# Thermometer.net
KiCad netlist of a schematic drawn in Altium Designer
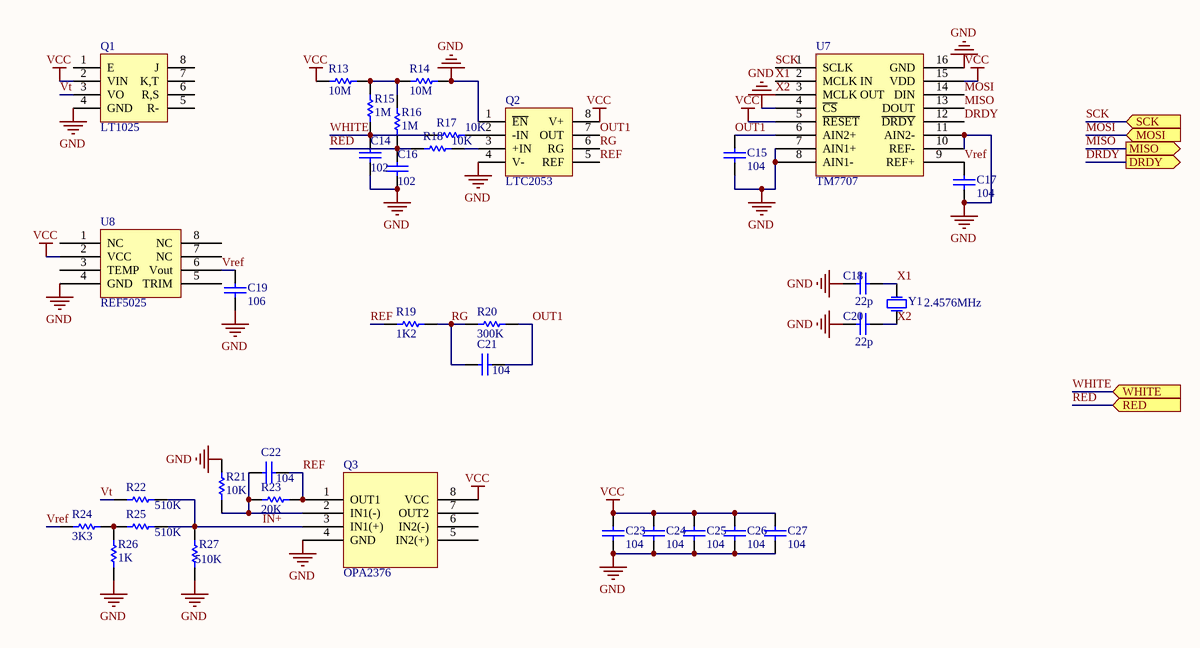
[diagram p0: Thermometer.SchDoc]

(export (version "E")
  (design (tool "Eeschema 10.0.6"))
  (components
    (comp (ref "C14")
      (value "102")
      (footprint "CR2012-0805")
      (description "Capacitor")
      (fields (field (name "Comment") "Cap") (field (name "PUBLISHER") "Altium Limited"))
      (libsource (lib "ComDev") (part "Cap"))
    )
    (comp (ref "C15")
      (value "104")
      (footprint "CR2012-0805")
      (description "Capacitor")
      (fields (field (name "Comment") "Cap") (field (name "PUBLISHER") "Altium Limited"))
      (libsource (lib "ComDev") (part "Cap"))
    )
    (comp (ref "C16")
      (value "102")
      (footprint "CR2012-0805")
      (description "Capacitor")
      (fields (field (name "Comment") "Cap") (field (name "PUBLISHER") "Altium Limited"))
      (libsource (lib "ComDev") (part "Cap"))
    )
    (comp (ref "C17")
      (value "104")
      (footprint "CR2012-0805")
      (description "Capacitor")
      (fields (field (name "Comment") "Cap") (field (name "PUBLISHER") "Altium Limited"))
      (libsource (lib "ComDev") (part "Cap"))
    )
    (comp (ref "C18")
      (value "22p")
      (footprint "CR2012-0805")
      (description "Capacitor")
      (fields (field (name "Comment") "Cap") (field (name "PUBLISHER") "Altium Limited"))
      (libsource (lib "ComDev") (part "Cap"))
    )
    (comp (ref "C19")
      (value "106")
      (footprint "CC3216-1206")
      (description "Capacitor")
      (fields (field (name "Comment") "Cap") (field (name "PUBLISHER") "Altium Limited"))
      (libsource (lib "ComDev") (part "Cap"))
    )
    (comp (ref "C20")
      (value "22p")
      (footprint "CR2012-0805")
      (description "Capacitor")
      (fields (field (name "Comment") "Cap") (field (name "PUBLISHER") "Altium Limited"))
      (libsource (lib "ComDev") (part "Cap"))
    )
    (comp (ref "C21")
      (value "104")
      (footprint "CR2012-0805")
      (description "Capacitor")
      (fields (field (name "Comment") "Cap") (field (name "PUBLISHER") "Altium Limited"))
      (libsource (lib "ComDev") (part "Cap"))
    )
    (comp (ref "C22")
      (value "104")
      (footprint "CR2012-0805")
      (description "Capacitor")
      (fields (field (name "Comment") "Cap") (field (name "PUBLISHER") "Altium Limited"))
      (libsource (lib "ComDev") (part "Cap"))
    )
    (comp (ref "C23")
      (value "104")
      (footprint "CR2012-0805")
      (description "Capacitor")
      (fields (field (name "Comment") "Cap") (field (name "PUBLISHER") "Altium Limited"))
      (libsource (lib "ComDev") (part "Cap"))
    )
    (comp (ref "C24")
      (value "104")
      (footprint "CR2012-0805")
      (description "Capacitor")
      (fields (field (name "Comment") "Cap") (field (name "PUBLISHER") "Altium Limited"))
      (libsource (lib "ComDev") (part "Cap"))
    )
    (comp (ref "C25")
      (value "104")
      (footprint "CR2012-0805")
      (description "Capacitor")
      (fields (field (name "Comment") "Cap") (field (name "PUBLISHER") "Altium Limited"))
      (libsource (lib "ComDev") (part "Cap"))
    )
    (comp (ref "C26")
      (value "104")
      (footprint "CR2012-0805")
      (description "Capacitor")
      (fields (field (name "Comment") "Cap") (field (name "PUBLISHER") "Altium Limited"))
      (libsource (lib "ComDev") (part "Cap"))
    )
    (comp (ref "C27")
      (value "104")
      (footprint "CR2012-0805")
      (description "Capacitor")
      (fields (field (name "Comment") "Cap") (field (name "PUBLISHER") "Altium Limited"))
      (libsource (lib "ComDev") (part "Cap"))
    )
    (comp (ref "Q1") (value "LT1025") (footprint "SO-G8") (libsource (lib "Sensor") (part "LT1025")))
    (comp (ref "Q2") (value "LTC2053") (footprint "MSOP-8") (libsource (lib "AMP") (part "LTC2053")))
    (comp (ref "Q3") (value "OPA2376") (footprint "SO-G8") (libsource (lib "AMP") (part "Double_AMP")))
    (comp (ref "R13")
      (value "10M")
      (footprint "CR2012-0805")
      (description "Resistor")
      (fields (field (name "Comment") "Res") (field (name "PUBLISHER") "Altium Limited"))
      (libsource (lib "ComDev") (part "Res"))
    )
    (comp (ref "R14")
      (value "10M")
      (footprint "CR2012-0805")
      (description "Resistor")
      (fields (field (name "Comment") "Res") (field (name "PUBLISHER") "Altium Limited"))
      (libsource (lib "ComDev") (part "Res"))
    )
    (comp (ref "R15")
      (value "1M")
      (footprint "CR2012-0805")
      (description "Resistor")
      (fields (field (name "Comment") "Res") (field (name "PUBLISHER") "Altium Limited"))
      (libsource (lib "ComDev") (part "Res"))
    )
    (comp (ref "R16")
      (value "1M")
      (footprint "CR2012-0805")
      (description "Resistor")
      (fields (field (name "Comment") "Res") (field (name "PUBLISHER") "Altium Limited"))
      (libsource (lib "ComDev") (part "Res"))
    )
    (comp (ref "R17")
      (value "10K")
      (footprint "CR2012-0805")
      (description "Resistor")
      (fields (field (name "Comment") "Res") (field (name "PUBLISHER") "Altium Limited"))
      (libsource (lib "ComDev") (part "Res"))
    )
    (comp (ref "R18")
      (value "10K")
      (footprint "CR2012-0805")
      (description "Resistor")
      (fields (field (name "Comment") "Res") (field (name "PUBLISHER") "Altium Limited"))
      (libsource (lib "ComDev") (part "Res"))
    )
    (comp (ref "R19")
      (value "1K2")
      (footprint "CR2012-0805")
      (description "Resistor")
      (fields (field (name "Comment") "Res") (field (name "PUBLISHER") "Altium Limited"))
      (libsource (lib "ComDev") (part "Res"))
    )
    (comp (ref "R20")
      (value "300K")
      (footprint "CR2012-0805")
      (description "Resistor")
      (fields (field (name "Comment") "Res") (field (name "PUBLISHER") "Altium Limited"))
      (libsource (lib "ComDev") (part "Res"))
    )
    (comp (ref "R21")
      (value "10K")
      (footprint "CR2012-0805")
      (description "Resistor")
      (fields (field (name "Comment") "Res") (field (name "PUBLISHER") "Altium Limited"))
      (libsource (lib "ComDev") (part "Res"))
    )
    (comp (ref "R22")
      (value "510K")
      (footprint "CR2012-0805")
      (description "Resistor")
      (fields (field (name "Comment") "Res") (field (name "PUBLISHER") "Altium Limited"))
      (libsource (lib "ComDev") (part "Res"))
    )
    (comp (ref "R23")
      (value "20K")
      (footprint "CR2012-0805")
      (description "Resistor")
      (fields (field (name "Comment") "Res") (field (name "PUBLISHER") "Altium Limited"))
      (libsource (lib "ComDev") (part "Res"))
    )
    (comp (ref "R24")
      (value "3K3")
      (footprint "CR2012-0805")
      (description "Resistor")
      (fields (field (name "Comment") "Res") (field (name "PUBLISHER") "Altium Limited"))
      (libsource (lib "ComDev") (part "Res"))
    )
    (comp (ref "R25")
      (value "510K")
      (footprint "CR2012-0805")
      (description "Resistor")
      (fields (field (name "Comment") "Res") (field (name "PUBLISHER") "Altium Limited"))
      (libsource (lib "ComDev") (part "Res"))
    )
    (comp (ref "R26")
      (value "1K")
      (footprint "CR2012-0805")
      (description "Resistor")
      (fields (field (name "Comment") "Res") (field (name "PUBLISHER") "Altium Limited"))
      (libsource (lib "ComDev") (part "Res"))
    )
    (comp (ref "R27")
      (value "510K")
      (footprint "CR2012-0805")
      (description "Resistor")
      (fields (field (name "Comment") "Res") (field (name "PUBLISHER") "Altium Limited"))
      (libsource (lib "ComDev") (part "Res"))
    )
    (comp (ref "U7") (value "TM7707") (footprint "SO-G16/D10") (libsource (lib "adc") (part "TM7707")))
    (comp (ref "U8") (value "REF5025") (footprint "SO-G8") (libsource (lib "Power") (part "REF5025")))
    (comp (ref "Y1")
      (value "XTAL")
      (footprint "XTAL")
      (description "Crystal Oscillator")
      (fields (field (name "FREQUANCY") "2.4576MHz") (field (name "PUBLISHER") "Altium Limited"))
      (libsource (lib "ComDev") (part "XTAL"))
    )
  )
  (nets
    (net (code "1") (name "/DRDY") (class "Default")
      (node (ref "U7") (pin "12") (pinfunction "~{DRDY}_12") (pintype "passive"))
    )
    (net (code "2") (name "/IN+") (class "Default")
      (node (ref "Q3") (pin "3") (pinfunction "IN1(+)_3") (pintype "passive"))
      (node (ref "R22") (pin "2") (pinfunction "2_2") (pintype "passive"))
      (node (ref "R25") (pin "2") (pinfunction "2_2") (pintype "passive"))
      (node (ref "R27") (pin "2") (pinfunction "2_2") (pintype "passive"))
    )
    (net (code "3") (name "/MISO") (class "Default")
      (node (ref "U7") (pin "13") (pinfunction "DOUT_13") (pintype "passive"))
    )
    (net (code "4") (name "/MOSI") (class "Default")
      (node (ref "U7") (pin "14") (pinfunction "DIN_14") (pintype "passive"))
    )
    (net (code "5") (name "/OUT1") (class "Default")
      (node (ref "C15") (pin "1") (pinfunction "1_1") (pintype "passive"))
      (node (ref "C21") (pin "1") (pinfunction "1_1") (pintype "passive"))
      (node (ref "Q2") (pin "7") (pinfunction "OUT_7") (pintype "passive"))
      (node (ref "R20") (pin "2") (pinfunction "2_2") (pintype "passive"))
      (node (ref "U7") (pin "6") (pinfunction "AIN2+_6") (pintype "passive"))
    )
    (net (code "6") (name "/RED") (class "Default")
      (node (ref "C16") (pin "2") (pinfunction "2_2") (pintype "passive"))
      (node (ref "R16") (pin "1") (pinfunction "1_1") (pintype "passive"))
      (node (ref "R18") (pin "1") (pinfunction "1_1") (pintype "passive"))
    )
    (net (code "7") (name "/REF") (class "Default")
      (node (ref "C22") (pin "1") (pinfunction "1_1") (pintype "passive"))
      (node (ref "Q2") (pin "5") (pinfunction "REF_5") (pintype "passive"))
      (node (ref "Q3") (pin "1") (pinfunction "OUT1_1") (pintype "passive"))
      (node (ref "R19") (pin "1") (pinfunction "1_1") (pintype "passive"))
      (node (ref "R23") (pin "1") (pinfunction "1_1") (pintype "passive"))
    )
    (net (code "8") (name "/RG") (class "Default")
      (node (ref "C21") (pin "2") (pinfunction "2_2") (pintype "passive"))
      (node (ref "Q2") (pin "6") (pinfunction "RG_6") (pintype "passive"))
      (node (ref "R19") (pin "2") (pinfunction "2_2") (pintype "passive"))
      (node (ref "R20") (pin "1") (pinfunction "1_1") (pintype "passive"))
    )
    (net (code "9") (name "/SCK") (class "Default")
      (node (ref "U7") (pin "1") (pinfunction "SCLK_1") (pintype "passive"))
    )
    (net (code "10") (name "/Vref") (class "Default")
      (node (ref "C17") (pin "2") (pinfunction "2_2") (pintype "passive"))
      (node (ref "C19") (pin "2") (pinfunction "2_2") (pintype "passive"))
      (node (ref "R24") (pin "1") (pinfunction "1_1") (pintype "passive"))
      (node (ref "U7") (pin "9") (pinfunction "REF+_9") (pintype "passive"))
      (node (ref "U8") (pin "6") (pinfunction "Vout_6") (pintype "passive"))
    )
    (net (code "11") (name "/Vt") (class "Default")
      (node (ref "Q1") (pin "3") (pinfunction "VO_3") (pintype "passive"))
      (node (ref "R22") (pin "1") (pinfunction "1_1") (pintype "passive"))
    )
    (net (code "12") (name "/WHITE") (class "Default")
      (node (ref "C14") (pin "2") (pinfunction "2_2") (pintype "passive"))
      (node (ref "R15") (pin "1") (pinfunction "1_1") (pintype "passive"))
      (node (ref "R17") (pin "1") (pinfunction "1_1") (pintype "passive"))
    )
    (net (code "13") (name "/X1") (class "Default")
      (node (ref "C18") (pin "2") (pinfunction "2_2") (pintype "passive"))
      (node (ref "U7") (pin "2") (pinfunction "MCLK_IN_2") (pintype "passive"))
      (node (ref "Y1") (pin "2") (pinfunction "OSC2_2") (pintype "passive"))
    )
    (net (code "14") (name "/X2") (class "Default")
      (node (ref "C20") (pin "2") (pinfunction "2_2") (pintype "passive"))
      (node (ref "U7") (pin "3") (pinfunction "MCLK_OUT_3") (pintype "passive"))
      (node (ref "Y1") (pin "1") (pinfunction "OSC1_1") (pintype "passive"))
    )
    (net (code "15") (name "GND") (class "Default")
      (node (ref "C14") (pin "1") (pinfunction "1_1") (pintype "passive"))
      (node (ref "C15") (pin "2") (pinfunction "2_2") (pintype "passive"))
      (node (ref "C16") (pin "1") (pinfunction "1_1") (pintype "passive"))
      (node (ref "C17") (pin "1") (pinfunction "1_1") (pintype "passive"))
      (node (ref "C18") (pin "1") (pinfunction "1_1") (pintype "passive"))
      (node (ref "C19") (pin "1") (pinfunction "1_1") (pintype "passive"))
      (node (ref "C20") (pin "1") (pinfunction "1_1") (pintype "passive"))
      (node (ref "C23") (pin "1") (pinfunction "1_1") (pintype "passive"))
      (node (ref "C24") (pin "1") (pinfunction "1_1") (pintype "passive"))
      (node (ref "C25") (pin "1") (pinfunction "1_1") (pintype "passive"))
      (node (ref "C26") (pin "1") (pinfunction "1_1") (pintype "passive"))
      (node (ref "C27") (pin "1") (pinfunction "1_1") (pintype "passive"))
      (node (ref "Q1") (pin "4") (pinfunction "GND_4") (pintype "passive"))
      (node (ref "Q2") (pin "1") (pinfunction "~{EN}_1") (pintype "passive"))
      (node (ref "Q2") (pin "4") (pinfunction "V-_4") (pintype "passive"))
      (node (ref "Q3") (pin "4") (pinfunction "GND_4") (pintype "passive"))
      (node (ref "R14") (pin "1") (pinfunction "1_1") (pintype "passive"))
      (node (ref "R21") (pin "2") (pinfunction "2_2") (pintype "passive"))
      (node (ref "R26") (pin "1") (pinfunction "1_1") (pintype "passive"))
      (node (ref "R27") (pin "1") (pinfunction "1_1") (pintype "passive"))
      (node (ref "U7") (pin "10") (pinfunction "REF-_10") (pintype "passive"))
      (node (ref "U7") (pin "11") (pinfunction "AIN2-_11") (pintype "passive"))
      (node (ref "U7") (pin "16") (pinfunction "GND_16") (pintype "passive"))
      (node (ref "U7") (pin "4") (pinfunction "~{CS}_4") (pintype "passive"))
      (node (ref "U7") (pin "7") (pinfunction "AIN1+_7") (pintype "passive"))
      (node (ref "U7") (pin "8") (pinfunction "AIN1-_8") (pintype "passive"))
      (node (ref "U8") (pin "4") (pinfunction "GND_4") (pintype "passive"))
    )
    (net (code "16") (name "Net-(Q2-+IN)") (class "Default")
      (node (ref "Q2") (pin "3") (pinfunction "+IN_3") (pintype "passive"))
      (node (ref "R18") (pin "2") (pinfunction "2_2") (pintype "passive"))
    )
    (net (code "17") (name "Net-(Q2--IN)") (class "Default")
      (node (ref "Q2") (pin "2") (pinfunction "-IN_2") (pintype "passive"))
      (node (ref "R17") (pin "2") (pinfunction "2_2") (pintype "passive"))
    )
    (net (code "18") (name "Net-(Q3-IN1(-))") (class "Default")
      (node (ref "C22") (pin "2") (pinfunction "2_2") (pintype "passive"))
      (node (ref "Q3") (pin "2") (pinfunction "IN1(-)_2") (pintype "passive"))
      (node (ref "R21") (pin "1") (pinfunction "1_1") (pintype "passive"))
      (node (ref "R23") (pin "2") (pinfunction "2_2") (pintype "passive"))
    )
    (net (code "19") (name "Net-(R13-Pad1)") (class "Default")
      (node (ref "R13") (pin "1") (pinfunction "1_1") (pintype "passive"))
      (node (ref "R14") (pin "2") (pinfunction "2_2") (pintype "passive"))
      (node (ref "R15") (pin "2") (pinfunction "2_2") (pintype "passive"))
      (node (ref "R16") (pin "2") (pinfunction "2_2") (pintype "passive"))
    )
    (net (code "20") (name "Net-(R24-Pad2)") (class "Default")
      (node (ref "R24") (pin "2") (pinfunction "2_2") (pintype "passive"))
      (node (ref "R25") (pin "1") (pinfunction "1_1") (pintype "passive"))
      (node (ref "R26") (pin "2") (pinfunction "2_2") (pintype "passive"))
    )
    (net (code "21") (name "VCC") (class "Default")
      (node (ref "C23") (pin "2") (pinfunction "2_2") (pintype "passive"))
      (node (ref "C24") (pin "2") (pinfunction "2_2") (pintype "passive"))
      (node (ref "C25") (pin "2") (pinfunction "2_2") (pintype "passive"))
      (node (ref "C26") (pin "2") (pinfunction "2_2") (pintype "passive"))
      (node (ref "C27") (pin "2") (pinfunction "2_2") (pintype "passive"))
      (node (ref "Q1") (pin "2") (pinfunction "VIN_2") (pintype "passive"))
      (node (ref "Q2") (pin "8") (pinfunction "V+_8") (pintype "passive"))
      (node (ref "Q3") (pin "8") (pinfunction "VCC_8") (pintype "passive"))
      (node (ref "R13") (pin "2") (pinfunction "2_2") (pintype "passive"))
      (node (ref "U7") (pin "15") (pinfunction "VDD_15") (pintype "passive"))
      (node (ref "U7") (pin "5") (pinfunction "~{RESET}_5") (pintype "passive"))
      (node (ref "U8") (pin "2") (pinfunction "VCC_2") (pintype "passive"))
    )
    (net (code "22") (name "unconnected-(Q1-E-Pad1)") (class "Default")
      (node (ref "Q1") (pin "1") (pinfunction "E_1") (pintype "passive"))
    )
    (net (code "23") (name "unconnected-(Q1-J-Pad8)") (class "Default")
      (node (ref "Q1") (pin "8") (pinfunction "J_8") (pintype "passive"))
    )
    (net (code "24") (name "unconnected-(Q1-K,T-Pad7)") (class "Default")
      (node (ref "Q1") (pin "7") (pinfunction "K,T_7") (pintype "passive"))
    )
    (net (code "25") (name "unconnected-(Q1-R,S-Pad6)") (class "Default")
      (node (ref "Q1") (pin "6") (pinfunction "R,S_6") (pintype "passive"))
    )
    (net (code "26") (name "unconnected-(Q1-R--Pad5)") (class "Default")
      (node (ref "Q1") (pin "5") (pinfunction "R-_5") (pintype "passive"))
    )
    (net (code "27") (name "unconnected-(Q3-IN2(+)-Pad5)") (class "Default")
      (node (ref "Q3") (pin "5") (pinfunction "IN2(+)_5") (pintype "passive"))
    )
    (net (code "28") (name "unconnected-(Q3-IN2(-)-Pad6)") (class "Default")
      (node (ref "Q3") (pin "6") (pinfunction "IN2(-)_6") (pintype "passive"))
    )
    (net (code "29") (name "unconnected-(Q3-OUT2-Pad7)") (class "Default")
      (node (ref "Q3") (pin "7") (pinfunction "OUT2_7") (pintype "passive"))
    )
    (net (code "30") (name "unconnected-(U8-NC-Pad1)") (class "Default")
      (node (ref "U8") (pin "1") (pinfunction "NC_1") (pintype "passive"))
    )
    (net (code "31") (name "unconnected-(U8-NC-Pad7)") (class "Default")
      (node (ref "U8") (pin "7") (pinfunction "NC_7") (pintype "passive"))
    )
    (net (code "32") (name "unconnected-(U8-NC-Pad8)") (class "Default")
      (node (ref "U8") (pin "8") (pinfunction "NC_8") (pintype "passive"))
    )
    (net (code "33") (name "unconnected-(U8-TEMP-Pad3)") (class "Default")
      (node (ref "U8") (pin "3") (pinfunction "TEMP_3") (pintype "passive"))
    )
    (net (code "34") (name "unconnected-(U8-TRIM-Pad5)") (class "Default")
      (node (ref "U8") (pin "5") (pinfunction "TRIM_5") (pintype "passive"))
    )
  )
)
